# Schematic_diagram-EDA.net
KiCad netlist of a schematic drawn in EasyEDA
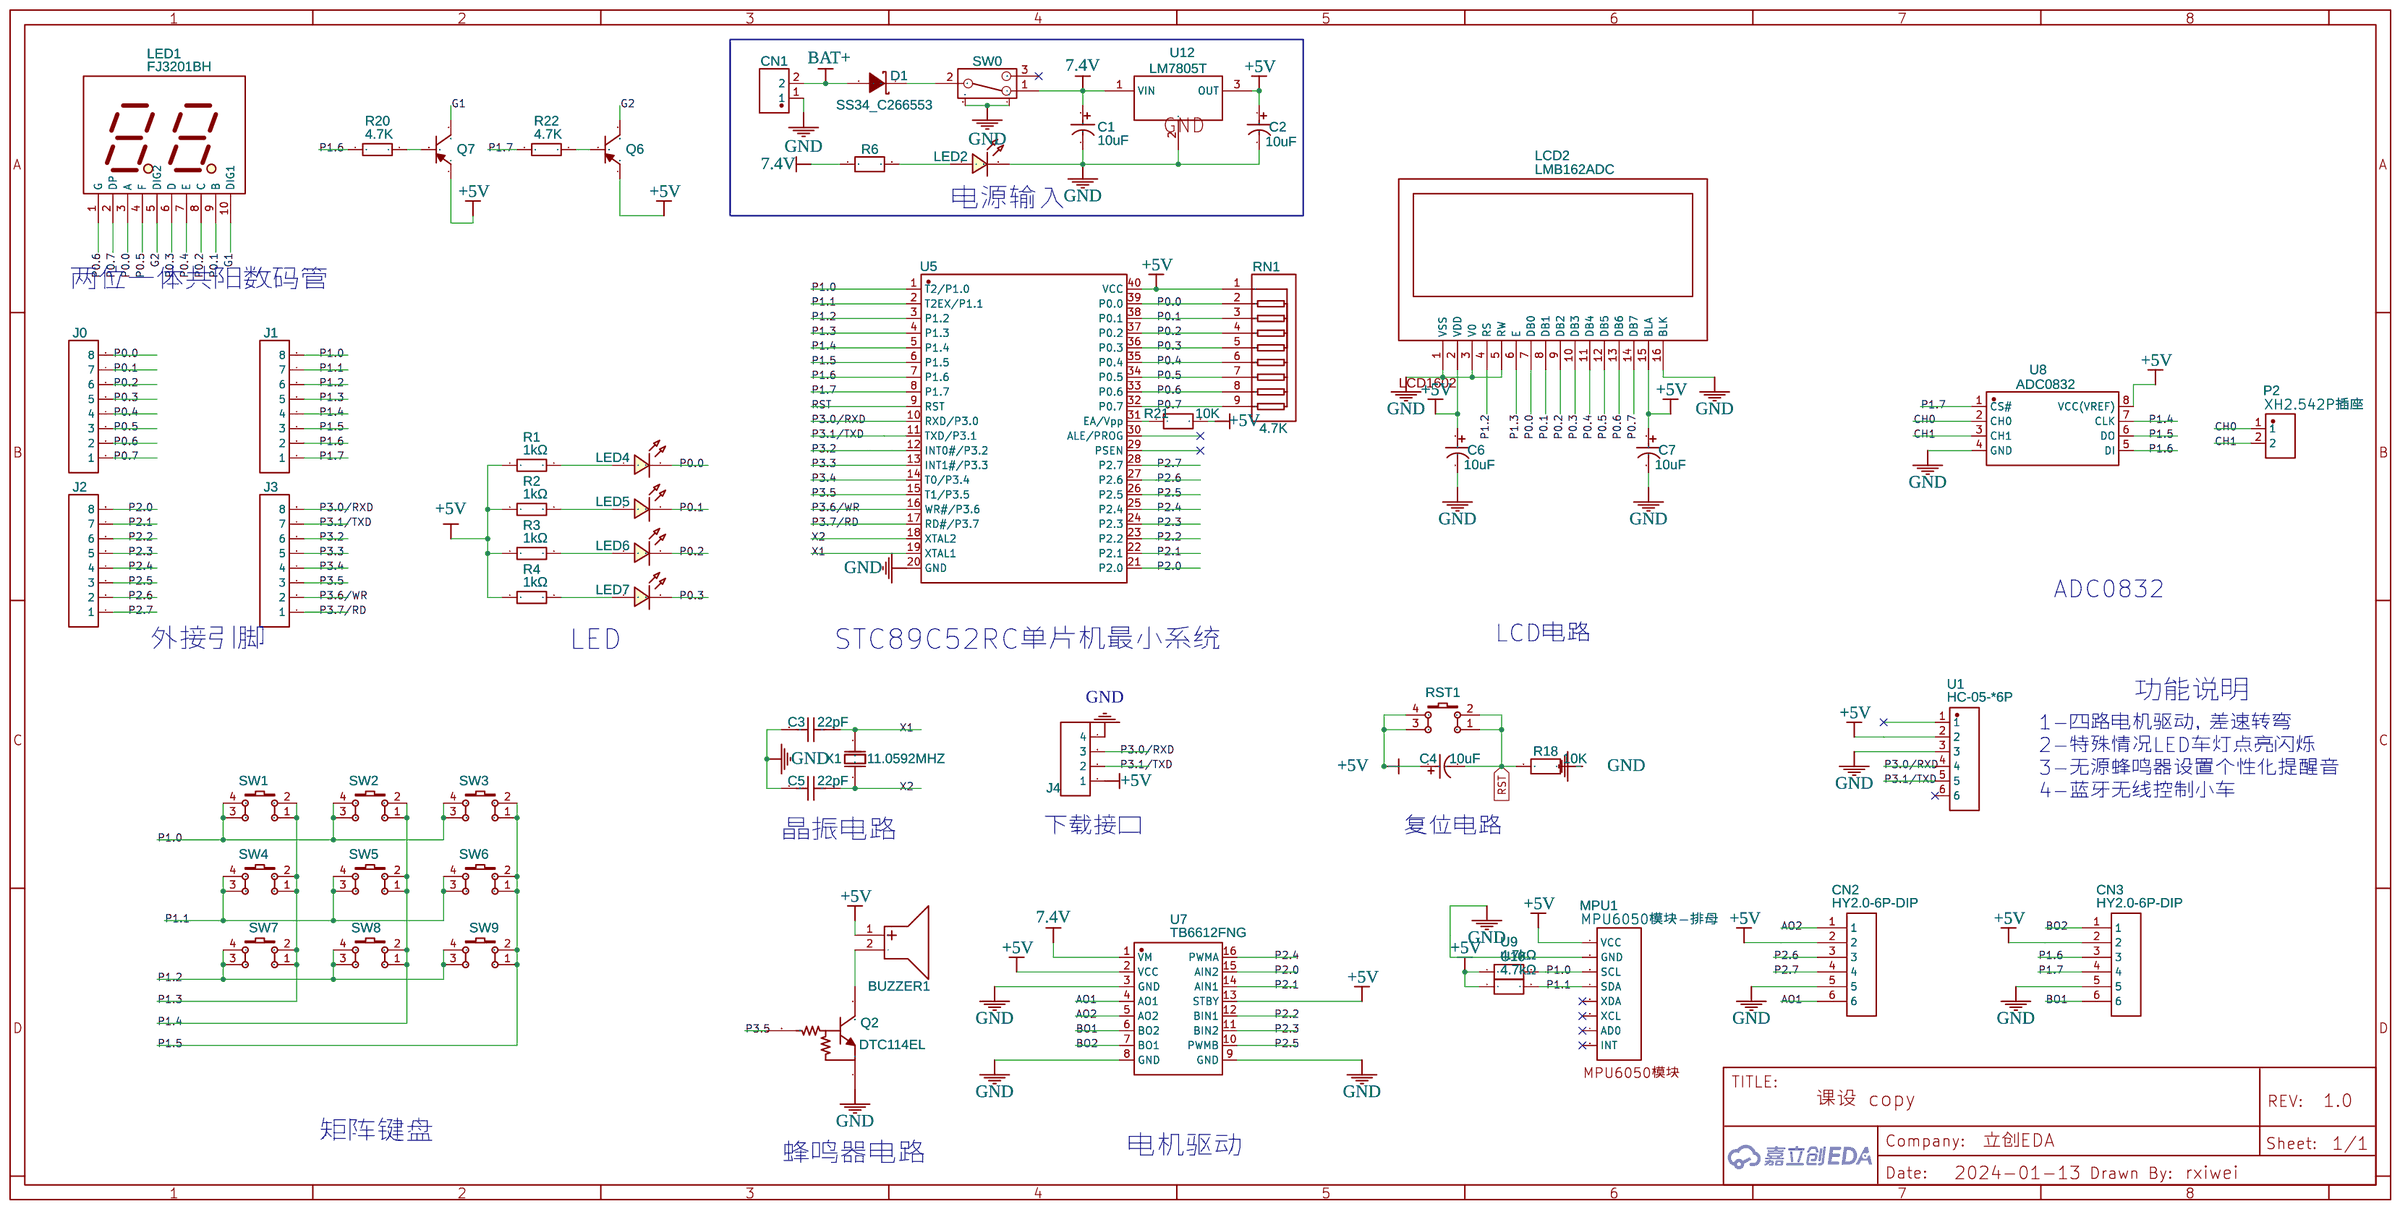
[diagram p0: schematic sheet]

(export (version "E")
  (design (tool "Eeschema 10.0.6"))
  (components
    (comp (ref "BUZZER1")
      (value "YS-MBZ9042C05R42")
      (fields (field (name "Manufacturer") "Fengming"))
      (libsource (lib "") (part "YS-MBZ9042C05R42"))
    )
    (comp (ref "C1")
      (value "10uF")
      (fields (field (name "Manufacturer Part") "10uF 25V 4*7") (field (name "Manufacturer") "ValuePro"))
      (libsource (lib "") (part "10uF 25V 4*7_1"))
    )
    (comp (ref "C2")
      (value "10uF")
      (fields (field (name "Manufacturer Part") "10uF 25V 4*7") (field (name "Manufacturer") "ValuePro"))
      (libsource (lib "") (part "10uF 25V 4*7_1"))
    )
    (comp (ref "C3") (value "22pF") (libsource (lib "") (part "CC81-N5U2J1B220KSEW")))
    (comp (ref "C4")
      (value "10uF")
      (fields (field (name "Manufacturer Part") "10uF 25V 4*7") (field (name "Manufacturer") "ValuePro"))
      (libsource (lib "") (part "10uF 25V 4*7"))
    )
    (comp (ref "C5") (value "22pF") (libsource (lib "") (part "CC81-N5U2J1B220KSEW")))
    (comp (ref "C6")
      (value "10uF")
      (fields (field (name "Manufacturer Part") "10uF 25V 4*7") (field (name "Manufacturer") "ValuePro"))
      (libsource (lib "") (part "10uF 25V 4*7_1"))
    )
    (comp (ref "C7")
      (value "10uF")
      (fields (field (name "Manufacturer Part") "10uF 25V 4*7") (field (name "Manufacturer") "ValuePro"))
      (libsource (lib "") (part "10uF 25V 4*7_1"))
    )
    (comp (ref "CN1")
      (value "XH-2A_C722856")
      (fields (field (name "Manufacturer Part") "XH-2A") (field (name "Manufacturer") "CAX"))
      (libsource (lib "") (part "XH-2A_C722856"))
    )
    (comp (ref "CN2") (value "HY2.0-6P-DIP") (libsource (lib "") (part "HY2.0-6P-DIP")))
    (comp (ref "CN3") (value "HY2.0-6P-DIP") (libsource (lib "") (part "HY2.0-6P-DIP")))
    (comp (ref "D1")
      (value "SS34_C266553")
      (fields
        (field (name "Manufacturer Part") "SS34")
        (field (name "Manufacturer") "Bourne Semicon (Shenzhen)")
      )
      (libsource (lib "") (part "SS34_C266553"))
    )
    (comp (ref "J0") (value "HDR-M-2.54_1x8") (libsource (lib "") (part "HDR-M-2.54_1x8")))
    (comp (ref "J1") (value "HDR-M-2.54_1x8") (libsource (lib "") (part "HDR-M-2.54_1x8")))
    (comp (ref "J2") (value "HDR-M-2.54_1x8") (libsource (lib "") (part "HDR-M-2.54_1x8")))
    (comp (ref "J3") (value "HDR-M-2.54_1x8") (libsource (lib "") (part "HDR-M-2.54_1x8")))
    (comp (ref "J4") (value "HDR-M-2.54_1x4") (libsource (lib "") (part "HDR-M-2.54_1x4")))
    (comp (ref "LCD2")
      (value "LMB162ADC")
      (fields (field (name "Manufacturer") "TOPWAY"))
      (libsource (lib "") (part "LMB162ADC"))
    )
    (comp (ref "LED1")
      (value "FJ3201BH")
      (fields (field (name "Manufacturer") "志浩"))
      (libsource (lib "") (part "FJ3201BH"))
    )
    (comp (ref "LED2")
      (value "LED-TH-3mm_R")
      (fields
        (field (name "Manufacturer Part") "204-10SDRD/S530-A3-L")
        (field (name "Manufacturer") "EVERLIGHT(台湾亿光)")
      )
      (libsource (lib "") (part "LED-TH-3mm_R"))
    )
    (comp (ref "LED4")
      (value "LED-TH-3mm_R")
      (fields
        (field (name "Manufacturer Part") "204-10SDRD/S530-A3-L")
        (field (name "Manufacturer") "EVERLIGHT(台湾亿光)")
      )
      (libsource (lib "") (part "LED-TH-3mm_R"))
    )
    (comp (ref "LED5")
      (value "LED-TH-3mm_R")
      (fields
        (field (name "Manufacturer Part") "204-10SDRD/S530-A3-L")
        (field (name "Manufacturer") "EVERLIGHT(台湾亿光)")
      )
      (libsource (lib "") (part "LED-TH-3mm_R"))
    )
    (comp (ref "LED6")
      (value "LED-TH-3mm_R")
      (fields
        (field (name "Manufacturer Part") "204-10SDRD/S530-A3-L")
        (field (name "Manufacturer") "EVERLIGHT(台湾亿光)")
      )
      (libsource (lib "") (part "LED-TH-3mm_R"))
    )
    (comp (ref "LED7")
      (value "LED-TH-3mm_R")
      (fields
        (field (name "Manufacturer Part") "204-10SDRD/S530-A3-L")
        (field (name "Manufacturer") "EVERLIGHT(台湾亿光)")
      )
      (libsource (lib "") (part "LED-TH-3mm_R"))
    )
    (comp (ref "MPU1") (value "MPU6050模块-排母") (libsource (lib "") (part "MPU6050模块-排母")))
    (comp (ref "P2") (value "XH2.542P插座") (libsource (lib "") (part "XH2.542P插座")))
    (comp (ref "Q2")
      (value "DTC114EL")
      (fields (field (name "Manufacturer Part") "DTC114EL-T92-K") (field (name "Manufacturer") "UTC"))
      (libsource (lib "") (part "DTC114EL-T92-K"))
    )
    (comp (ref "Q6")
      (value "2N3906(SOT-23)")
      (fields (field (name "Manufacturer Part") "2N3906S-RTK/PS") (field (name "Manufacturer") "KEC"))
      (libsource (lib "") (part "2N3906(SOT-23)"))
    )
    (comp (ref "Q7")
      (value "2N3906(SOT-23)")
      (fields (field (name "Manufacturer Part") "2N3906S-RTK/PS") (field (name "Manufacturer") "KEC"))
      (libsource (lib "") (part "2N3906(SOT-23)"))
    )
    (comp (ref "R1")
      (value "1kΩ")
      (fields (field (name "Manufacturer Part") "MOF3WS-1KΩ±5%T") (field (name "Manufacturer") "华星机电"))
      (libsource (lib "") (part "MOF3WS-1KΩ±5%T"))
    )
    (comp (ref "R2")
      (value "1kΩ")
      (fields (field (name "Manufacturer Part") "MOF3WS-1KΩ±5%T") (field (name "Manufacturer") "华星机电"))
      (libsource (lib "") (part "MOF3WS-1KΩ±5%T"))
    )
    (comp (ref "R3")
      (value "1kΩ")
      (fields (field (name "Manufacturer Part") "MOF3WS-1KΩ±5%T") (field (name "Manufacturer") "华星机电"))
      (libsource (lib "") (part "MOF3WS-1KΩ±5%T"))
    )
    (comp (ref "R4")
      (value "1kΩ")
      (fields (field (name "Manufacturer Part") "MOF3WS-1KΩ±5%T") (field (name "Manufacturer") "华星机电"))
      (libsource (lib "") (part "MOF3WS-1KΩ±5%T"))
    )
    (comp (ref "R6")
      (value "10K")
      (fields (field (name "Manufacturer Part") "RN 1/4W 10K F T/B A1") (field (name "Manufacturer") "TyoHM"))
      (libsource (lib "") (part "RN 1/4W 10K F T/B A1"))
    )
    (comp (ref "R18")
      (value "10K")
      (fields (field (name "Manufacturer Part") "RN 1/4W 10K F T/B A1") (field (name "Manufacturer") "TyoHM"))
      (libsource (lib "") (part "RN 1/4W 10K F T/B A1_1"))
    )
    (comp (ref "R20")
      (value "4.7K")
      (fields
        (field (name "Manufacturer Part") "RSS02J1001A520NH")
        (field (name "Manufacturer") "Futaba Elec")
      )
      (libsource (lib "") (part "RSS02J1001A520NH"))
    )
    (comp (ref "R21")
      (value "10K")
      (fields (field (name "Manufacturer Part") "RN 1/4W 10K F T/B A1") (field (name "Manufacturer") "TyoHM"))
      (libsource (lib "") (part "RN 1/4W 10K F T/B A1"))
    )
    (comp (ref "R22")
      (value "4.7K")
      (fields
        (field (name "Manufacturer Part") "RSS02J1001A520NH")
        (field (name "Manufacturer") "Futaba Elec")
      )
      (libsource (lib "") (part "RSS02J1001A520NH"))
    )
    (comp (ref "RN1")
      (value "4.7K")
      (fields (field (name "Manufacturer Part") "A09-472JP") (field (name "Manufacturer") "FH"))
      (libsource (lib "") (part "A09-472JP"))
    )
    (comp (ref "RST1")
      (value "K4-6×6_TH")
      (fields (field (name "Manufacturer Part") "K2-1102DP-E4SW-04") (field (name "Manufacturer") "韩国韩荣"))
      (libsource (lib "") (part "K4-6×6_TH_1"))
    )
    (comp (ref "SW0")
      (value "SK-12E12-G5")
      (fields (field (name "Manufacturer") "Rectangular Connectors - Contacts"))
      (libsource (lib "") (part "SK-12E12-G5"))
    )
    (comp (ref "SW1")
      (value "K4-6×6_TH")
      (fields (field (name "Manufacturer Part") "K2-1102DP-E4SW-04") (field (name "Manufacturer") "韩国韩荣"))
      (libsource (lib "") (part "K4-6×6_TH"))
    )
    (comp (ref "SW2")
      (value "K4-6×6_TH")
      (fields (field (name "Manufacturer Part") "K2-1102DP-E4SW-04") (field (name "Manufacturer") "韩国韩荣"))
      (libsource (lib "") (part "K4-6×6_TH"))
    )
    (comp (ref "SW3")
      (value "K4-6×6_TH")
      (fields (field (name "Manufacturer Part") "K2-1102DP-E4SW-04") (field (name "Manufacturer") "韩国韩荣"))
      (libsource (lib "") (part "K4-6×6_TH"))
    )
    (comp (ref "SW4")
      (value "K4-6×6_TH")
      (fields (field (name "Manufacturer Part") "K2-1102DP-E4SW-04") (field (name "Manufacturer") "韩国韩荣"))
      (libsource (lib "") (part "K4-6×6_TH"))
    )
    (comp (ref "SW5")
      (value "K4-6×6_TH")
      (fields (field (name "Manufacturer Part") "K2-1102DP-E4SW-04") (field (name "Manufacturer") "韩国韩荣"))
      (libsource (lib "") (part "K4-6×6_TH"))
    )
    (comp (ref "SW6")
      (value "K4-6×6_TH")
      (fields (field (name "Manufacturer Part") "K2-1102DP-E4SW-04") (field (name "Manufacturer") "韩国韩荣"))
      (libsource (lib "") (part "K4-6×6_TH"))
    )
    (comp (ref "SW7")
      (value "K4-6×6_TH")
      (fields (field (name "Manufacturer Part") "K2-1102DP-E4SW-04") (field (name "Manufacturer") "韩国韩荣"))
      (libsource (lib "") (part "K4-6×6_TH"))
    )
    (comp (ref "SW8")
      (value "K4-6×6_TH")
      (fields (field (name "Manufacturer Part") "K2-1102DP-E4SW-04") (field (name "Manufacturer") "韩国韩荣"))
      (libsource (lib "") (part "K4-6×6_TH"))
    )
    (comp (ref "SW9")
      (value "K4-6×6_TH")
      (fields (field (name "Manufacturer Part") "K2-1102DP-E4SW-04") (field (name "Manufacturer") "韩国韩荣"))
      (libsource (lib "") (part "K4-6×6_TH"))
    )
    (comp (ref "U1")
      (value "HC-05-*6P")
      (fields (field (name "Manufacturer Part") "HC-05_排母*6P"))
      (libsource (lib "") (part "HC-05-*6P"))
    )
    (comp (ref "U5")
      (value "STC89C52RC-40I")
      (fields (field (name "Manufacturer") "STC"))
      (libsource (lib "") (part "STC89C52RC-40I"))
    )
    (comp (ref "U7") (value "TB6612FNG") (libsource (lib "") (part "TB6612FNG")))
    (comp (ref "U8")
      (value "ADC0832")
      (fields (field (name "Manufacturer Part") "ADC0832CCN/NOPB") (field (name "Manufacturer") "TI(德州仪器)"))
      (libsource (lib "") (part "ADC0832CCN/NOPB"))
    )
    (comp (ref "U9")
      (value "4.7kΩ")
      (fields (field (name "Manufacturer Part") "FMF200FRE73-4K7") (field (name "Manufacturer") "YAGEO(国巨)"))
      (libsource (lib "") (part "FMF200FRE73-4K7"))
    )
    (comp (ref "U10")
      (value "4.7kΩ")
      (fields (field (name "Manufacturer Part") "FMF200FRE73-4K7") (field (name "Manufacturer") "YAGEO(国巨)"))
      (libsource (lib "") (part "FMF200FRE73-4K7"))
    )
    (comp (ref "U12")
      (value "LM7805T")
      (fields (field (name "Manufacturer") "HGC(Huaguan Semicon)"))
      (libsource (lib "") (part "LM7805T"))
    )
    (comp (ref "X1")
      (value "11.0592MHZ")
      (fields
        (field (name "Manufacturer Part") "XIHCCCNANF-11.0592")
        (field (name "Manufacturer") "TAITIEN Elec")
      )
      (libsource (lib "") (part "XIHCCCNANF-11.0592"))
    )
  )
  (nets
    (net (code "1") (name "+5V") (class "Default")
      (node (ref "BUZZER1") (pin "1") (pinfunction "+_1") (pintype "unspecified"))
      (node (ref "C2") (pin "1") (pinfunction "1_1") (pintype "input"))
      (node (ref "C4") (pin "1") (pinfunction "1_1") (pintype "input"))
      (node (ref "C6") (pin "1") (pinfunction "1_1") (pintype "input"))
      (node (ref "C7") (pin "1") (pinfunction "1_1") (pintype "input"))
      (node (ref "CN2") (pin "2") (pinfunction "2_2") (pintype "unspecified"))
      (node (ref "CN3") (pin "2") (pinfunction "2_2") (pintype "unspecified"))
      (node (ref "J4") (pin "1") (pinfunction "1_1") (pintype "unspecified"))
      (node (ref "LCD2") (pin "15") (pinfunction "BLA_15") (pintype "unspecified"))
      (node (ref "LCD2") (pin "2") (pinfunction "VDD_2") (pintype "unspecified"))
      (node (ref "MPU1") (pin "1") (pinfunction "VCC_1") (pintype "unspecified"))
      (node (ref "Q6") (pin "1") (pinfunction "E_1") (pintype "input"))
      (node (ref "Q7") (pin "1") (pinfunction "E_1") (pintype "input"))
      (node (ref "R1") (pin "1") (pinfunction "1_1") (pintype "unspecified"))
      (node (ref "R2") (pin "1") (pinfunction "1_1") (pintype "unspecified"))
      (node (ref "R21") (pin "2") (pinfunction "2_2") (pintype "unspecified"))
      (node (ref "R3") (pin "1") (pinfunction "1_1") (pintype "unspecified"))
      (node (ref "R4") (pin "1") (pinfunction "1_1") (pintype "unspecified"))
      (node (ref "RN1") (pin "1") (pinfunction "1_1") (pintype "unspecified"))
      (node (ref "RST1") (pin "3") (pinfunction "3_3") (pintype "unspecified"))
      (node (ref "RST1") (pin "4") (pinfunction "4_4") (pintype "unspecified"))
      (node (ref "U1") (pin "2") (pinfunction "2_2") (pintype "unspecified"))
      (node (ref "U10") (pin "1") (pinfunction "1_1") (pintype "unspecified"))
      (node (ref "U12") (pin "3") (pinfunction "OUT_3") (pintype "passive"))
      (node (ref "U5") (pin "40") (pinfunction "VCC_40") (pintype "unspecified"))
      (node (ref "U7") (pin "13") (pinfunction "STBY_13") (pintype "unspecified"))
      (node (ref "U7") (pin "2") (pinfunction "VCC_2") (pintype "unspecified"))
      (node (ref "U8") (pin "8") (pinfunction "VCC(VREF)_8") (pintype "unspecified"))
      (node (ref "U9") (pin "1") (pinfunction "1_1") (pintype "unspecified"))
    )
    (net (code "2") (name "/AO1") (class "Default")
      (node (ref "CN2") (pin "6") (pinfunction "6_6") (pintype "unspecified"))
      (node (ref "U7") (pin "4") (pinfunction "AO1_4") (pintype "unspecified"))
    )
    (net (code "3") (name "/AO2") (class "Default")
      (node (ref "CN2") (pin "1") (pinfunction "1_1") (pintype "unspecified"))
      (node (ref "U7") (pin "5") (pinfunction "AO2_5") (pintype "unspecified"))
    )
    (net (code "4") (name "/BO1") (class "Default")
      (node (ref "CN3") (pin "6") (pinfunction "6_6") (pintype "unspecified"))
      (node (ref "U7") (pin "6") (pinfunction "BO2_6") (pintype "unspecified"))
    )
    (net (code "5") (name "/BO2") (class "Default")
      (node (ref "CN3") (pin "1") (pinfunction "1_1") (pintype "unspecified"))
      (node (ref "U7") (pin "7") (pinfunction "BO1_7") (pintype "unspecified"))
    )
    (net (code "6") (name "/CH0") (class "Default")
      (node (ref "P2") (pin "1") (pinfunction "1_1") (pintype "unspecified"))
      (node (ref "U8") (pin "2") (pinfunction "CH0_2") (pintype "unspecified"))
    )
    (net (code "7") (name "/CH1") (class "Default")
      (node (ref "P2") (pin "2") (pinfunction "2_2") (pintype "unspecified"))
      (node (ref "U8") (pin "3") (pinfunction "CH1_3") (pintype "unspecified"))
    )
    (net (code "8") (name "/G1") (class "Default")
      (node (ref "LED1") (pin "10") (pinfunction "DIG1_10") (pintype "unspecified"))
      (node (ref "Q7") (pin "3") (pinfunction "C_3") (pintype "input"))
    )
    (net (code "9") (name "/G2") (class "Default")
      (node (ref "LED1") (pin "5") (pinfunction "DIG2_5") (pintype "unspecified"))
      (node (ref "Q6") (pin "3") (pinfunction "C_3") (pintype "input"))
    )
    (net (code "10") (name "/P0.0") (class "Default")
      (node (ref "J0") (pin "8") (pinfunction "8_8") (pintype "unspecified"))
      (node (ref "LCD2") (pin "7") (pinfunction "DB0_7") (pintype "unspecified"))
      (node (ref "LED1") (pin "3") (pinfunction "A_3") (pintype "unspecified"))
      (node (ref "LED4") (pin "2") (pinfunction "2_2") (pintype "unspecified"))
      (node (ref "RN1") (pin "2") (pinfunction "2_2") (pintype "unspecified"))
      (node (ref "U5") (pin "39") (pinfunction "P0.0_39") (pintype "unspecified"))
    )
    (net (code "11") (name "/P0.1") (class "Default")
      (node (ref "J0") (pin "7") (pinfunction "7_7") (pintype "unspecified"))
      (node (ref "LCD2") (pin "8") (pinfunction "DB1_8") (pintype "unspecified"))
      (node (ref "LED1") (pin "9") (pinfunction "B_9") (pintype "unspecified"))
      (node (ref "LED5") (pin "2") (pinfunction "2_2") (pintype "unspecified"))
      (node (ref "RN1") (pin "3") (pinfunction "3_3") (pintype "unspecified"))
      (node (ref "U5") (pin "38") (pinfunction "P0.1_38") (pintype "unspecified"))
    )
    (net (code "12") (name "/P0.2") (class "Default")
      (node (ref "J0") (pin "6") (pinfunction "6_6") (pintype "unspecified"))
      (node (ref "LCD2") (pin "9") (pinfunction "DB2_9") (pintype "unspecified"))
      (node (ref "LED1") (pin "8") (pinfunction "C_8") (pintype "unspecified"))
      (node (ref "LED6") (pin "2") (pinfunction "2_2") (pintype "unspecified"))
      (node (ref "RN1") (pin "4") (pinfunction "4_4") (pintype "unspecified"))
      (node (ref "U5") (pin "37") (pinfunction "P0.2_37") (pintype "unspecified"))
    )
    (net (code "13") (name "/P0.3") (class "Default")
      (node (ref "J0") (pin "5") (pinfunction "5_5") (pintype "unspecified"))
      (node (ref "LCD2") (pin "10") (pinfunction "DB3_10") (pintype "unspecified"))
      (node (ref "LED1") (pin "6") (pinfunction "D_6") (pintype "unspecified"))
      (node (ref "LED7") (pin "2") (pinfunction "2_2") (pintype "unspecified"))
      (node (ref "RN1") (pin "5") (pinfunction "5_5") (pintype "unspecified"))
      (node (ref "U5") (pin "36") (pinfunction "P0.3_36") (pintype "unspecified"))
    )
    (net (code "14") (name "/P0.4") (class "Default")
      (node (ref "J0") (pin "4") (pinfunction "4_4") (pintype "unspecified"))
      (node (ref "LCD2") (pin "11") (pinfunction "DB4_11") (pintype "unspecified"))
      (node (ref "LED1") (pin "7") (pinfunction "E_7") (pintype "unspecified"))
      (node (ref "RN1") (pin "6") (pinfunction "6_6") (pintype "unspecified"))
      (node (ref "U5") (pin "35") (pinfunction "P0.4_35") (pintype "unspecified"))
    )
    (net (code "15") (name "/P0.5") (class "Default")
      (node (ref "J0") (pin "3") (pinfunction "3_3") (pintype "unspecified"))
      (node (ref "LCD2") (pin "12") (pinfunction "DB5_12") (pintype "unspecified"))
      (node (ref "LED1") (pin "4") (pinfunction "F_4") (pintype "unspecified"))
      (node (ref "RN1") (pin "7") (pinfunction "7_7") (pintype "unspecified"))
      (node (ref "U5") (pin "34") (pinfunction "P0.5_34") (pintype "unspecified"))
    )
    (net (code "16") (name "/P0.6") (class "Default")
      (node (ref "J0") (pin "2") (pinfunction "2_2") (pintype "unspecified"))
      (node (ref "LCD2") (pin "13") (pinfunction "DB6_13") (pintype "unspecified"))
      (node (ref "LED1") (pin "1") (pinfunction "G_1") (pintype "unspecified"))
      (node (ref "RN1") (pin "8") (pinfunction "8_8") (pintype "unspecified"))
      (node (ref "U5") (pin "33") (pinfunction "P0.6_33") (pintype "unspecified"))
    )
    (net (code "17") (name "/P0.7") (class "Default")
      (node (ref "J0") (pin "1") (pinfunction "1_1") (pintype "unspecified"))
      (node (ref "LCD2") (pin "14") (pinfunction "DB7_14") (pintype "unspecified"))
      (node (ref "LED1") (pin "2") (pinfunction "DP_2") (pintype "unspecified"))
      (node (ref "RN1") (pin "9") (pinfunction "9_9") (pintype "unspecified"))
      (node (ref "U5") (pin "32") (pinfunction "P0.7_32") (pintype "unspecified"))
    )
    (net (code "18") (name "/P1.0") (class "Default")
      (node (ref "J1") (pin "8") (pinfunction "8_8") (pintype "unspecified"))
      (node (ref "MPU1") (pin "3") (pinfunction "SCL_3") (pintype "unspecified"))
      (node (ref "SW1") (pin "3") (pinfunction "3_3") (pintype "unspecified"))
      (node (ref "SW1") (pin "4") (pinfunction "4_4") (pintype "unspecified"))
      (node (ref "SW2") (pin "3") (pinfunction "3_3") (pintype "unspecified"))
      (node (ref "SW2") (pin "4") (pinfunction "4_4") (pintype "unspecified"))
      (node (ref "SW3") (pin "3") (pinfunction "3_3") (pintype "unspecified"))
      (node (ref "SW3") (pin "4") (pinfunction "4_4") (pintype "unspecified"))
      (node (ref "U5") (pin "1") (pinfunction "T2/P1.0_1") (pintype "unspecified"))
      (node (ref "U9") (pin "2") (pinfunction "2_2") (pintype "unspecified"))
    )
    (net (code "19") (name "/P1.1") (class "Default")
      (node (ref "J1") (pin "7") (pinfunction "7_7") (pintype "unspecified"))
      (node (ref "MPU1") (pin "4") (pinfunction "SDA_4") (pintype "unspecified"))
      (node (ref "SW4") (pin "3") (pinfunction "3_3") (pintype "unspecified"))
      (node (ref "SW4") (pin "4") (pinfunction "4_4") (pintype "unspecified"))
      (node (ref "SW5") (pin "3") (pinfunction "3_3") (pintype "unspecified"))
      (node (ref "SW5") (pin "4") (pinfunction "4_4") (pintype "unspecified"))
      (node (ref "SW6") (pin "3") (pinfunction "3_3") (pintype "unspecified"))
      (node (ref "SW6") (pin "4") (pinfunction "4_4") (pintype "unspecified"))
      (node (ref "U10") (pin "2") (pinfunction "2_2") (pintype "unspecified"))
      (node (ref "U5") (pin "2") (pinfunction "T2EX/P1.1_2") (pintype "unspecified"))
    )
    (net (code "20") (name "/P1.2") (class "Default")
      (node (ref "J1") (pin "6") (pinfunction "6_6") (pintype "unspecified"))
      (node (ref "LCD2") (pin "4") (pinfunction "RS_4") (pintype "unspecified"))
      (node (ref "SW7") (pin "3") (pinfunction "3_3") (pintype "unspecified"))
      (node (ref "SW7") (pin "4") (pinfunction "4_4") (pintype "unspecified"))
      (node (ref "SW8") (pin "3") (pinfunction "3_3") (pintype "unspecified"))
      (node (ref "SW8") (pin "4") (pinfunction "4_4") (pintype "unspecified"))
      (node (ref "SW9") (pin "3") (pinfunction "3_3") (pintype "unspecified"))
      (node (ref "SW9") (pin "4") (pinfunction "4_4") (pintype "unspecified"))
      (node (ref "U5") (pin "3") (pinfunction "P1.2_3") (pintype "unspecified"))
    )
    (net (code "21") (name "/P1.3") (class "Default")
      (node (ref "J1") (pin "5") (pinfunction "5_5") (pintype "unspecified"))
      (node (ref "LCD2") (pin "6") (pinfunction "E_6") (pintype "unspecified"))
      (node (ref "SW1") (pin "1") (pinfunction "1_1") (pintype "unspecified"))
      (node (ref "SW1") (pin "2") (pinfunction "2_2") (pintype "unspecified"))
      (node (ref "SW4") (pin "1") (pinfunction "1_1") (pintype "unspecified"))
      (node (ref "SW4") (pin "2") (pinfunction "2_2") (pintype "unspecified"))
      (node (ref "SW7") (pin "1") (pinfunction "1_1") (pintype "unspecified"))
      (node (ref "SW7") (pin "2") (pinfunction "2_2") (pintype "unspecified"))
      (node (ref "U5") (pin "4") (pinfunction "P1.3_4") (pintype "unspecified"))
    )
    (net (code "22") (name "/P1.4") (class "Default")
      (node (ref "J1") (pin "4") (pinfunction "4_4") (pintype "unspecified"))
      (node (ref "SW2") (pin "1") (pinfunction "1_1") (pintype "unspecified"))
      (node (ref "SW2") (pin "2") (pinfunction "2_2") (pintype "unspecified"))
      (node (ref "SW5") (pin "1") (pinfunction "1_1") (pintype "unspecified"))
      (node (ref "SW5") (pin "2") (pinfunction "2_2") (pintype "unspecified"))
      (node (ref "SW8") (pin "1") (pinfunction "1_1") (pintype "unspecified"))
      (node (ref "SW8") (pin "2") (pinfunction "2_2") (pintype "unspecified"))
      (node (ref "U5") (pin "5") (pinfunction "P1.4_5") (pintype "unspecified"))
      (node (ref "U8") (pin "7") (pinfunction "CLK_7") (pintype "unspecified"))
    )
    (net (code "23") (name "/P1.5") (class "Default")
      (node (ref "J1") (pin "3") (pinfunction "3_3") (pintype "unspecified"))
      (node (ref "SW3") (pin "1") (pinfunction "1_1") (pintype "unspecified"))
      (node (ref "SW3") (pin "2") (pinfunction "2_2") (pintype "unspecified"))
      (node (ref "SW6") (pin "1") (pinfunction "1_1") (pintype "unspecified"))
      (node (ref "SW6") (pin "2") (pinfunction "2_2") (pintype "unspecified"))
      (node (ref "SW9") (pin "1") (pinfunction "1_1") (pintype "unspecified"))
      (node (ref "SW9") (pin "2") (pinfunction "2_2") (pintype "unspecified"))
      (node (ref "U5") (pin "6") (pinfunction "P1.5_6") (pintype "unspecified"))
      (node (ref "U8") (pin "6") (pinfunction "DO_6") (pintype "unspecified"))
    )
    (net (code "24") (name "/P1.6") (class "Default")
      (node (ref "CN3") (pin "3") (pinfunction "3_3") (pintype "unspecified"))
      (node (ref "J1") (pin "2") (pinfunction "2_2") (pintype "unspecified"))
      (node (ref "R20") (pin "2") (pinfunction "2_2") (pintype "unspecified"))
      (node (ref "U5") (pin "7") (pinfunction "P1.6_7") (pintype "unspecified"))
      (node (ref "U8") (pin "5") (pinfunction "DI_5") (pintype "unspecified"))
    )
    (net (code "25") (name "/P1.7") (class "Default")
      (node (ref "CN3") (pin "4") (pinfunction "4_4") (pintype "unspecified"))
      (node (ref "J1") (pin "1") (pinfunction "1_1") (pintype "unspecified"))
      (node (ref "R22") (pin "2") (pinfunction "2_2") (pintype "unspecified"))
      (node (ref "U5") (pin "8") (pinfunction "P1.7_8") (pintype "unspecified"))
      (node (ref "U8") (pin "1") (pinfunction "CS#_1") (pintype "unspecified"))
    )
    (net (code "26") (name "/P2.0") (class "Default")
      (node (ref "J2") (pin "8") (pinfunction "8_8") (pintype "unspecified"))
      (node (ref "U5") (pin "21") (pinfunction "P2.0_21") (pintype "unspecified"))
      (node (ref "U7") (pin "15") (pinfunction "AIN2_15") (pintype "unspecified"))
    )
    (net (code "27") (name "/P2.1") (class "Default")
      (node (ref "J2") (pin "7") (pinfunction "7_7") (pintype "unspecified"))
      (node (ref "U5") (pin "22") (pinfunction "P2.1_22") (pintype "unspecified"))
      (node (ref "U7") (pin "14") (pinfunction "AIN1_14") (pintype "unspecified"))
    )
    (net (code "28") (name "/P2.2") (class "Default")
      (node (ref "J2") (pin "6") (pinfunction "6_6") (pintype "unspecified"))
      (node (ref "U5") (pin "23") (pinfunction "P2.2_23") (pintype "unspecified"))
      (node (ref "U7") (pin "12") (pinfunction "BIN1_12") (pintype "unspecified"))
    )
    (net (code "29") (name "/P2.3") (class "Default")
      (node (ref "J2") (pin "5") (pinfunction "5_5") (pintype "unspecified"))
      (node (ref "U5") (pin "24") (pinfunction "P2.3_24") (pintype "unspecified"))
      (node (ref "U7") (pin "11") (pinfunction "BIN2_11") (pintype "unspecified"))
    )
    (net (code "30") (name "/P2.4") (class "Default")
      (node (ref "J2") (pin "4") (pinfunction "4_4") (pintype "unspecified"))
      (node (ref "U5") (pin "25") (pinfunction "P2.4_25") (pintype "unspecified"))
      (node (ref "U7") (pin "16") (pinfunction "PWMA_16") (pintype "unspecified"))
    )
    (net (code "31") (name "/P2.5") (class "Default")
      (node (ref "J2") (pin "3") (pinfunction "3_3") (pintype "unspecified"))
      (node (ref "U5") (pin "26") (pinfunction "P2.5_26") (pintype "unspecified"))
      (node (ref "U7") (pin "10") (pinfunction "PWMB_10") (pintype "unspecified"))
    )
    (net (code "32") (name "/P2.6") (class "Default")
      (node (ref "CN2") (pin "3") (pinfunction "3_3") (pintype "unspecified"))
      (node (ref "J2") (pin "2") (pinfunction "2_2") (pintype "unspecified"))
      (node (ref "U5") (pin "27") (pinfunction "P2.6_27") (pintype "unspecified"))
    )
    (net (code "33") (name "/P2.7") (class "Default")
      (node (ref "CN2") (pin "4") (pinfunction "4_4") (pintype "unspecified"))
      (node (ref "J2") (pin "1") (pinfunction "1_1") (pintype "unspecified"))
      (node (ref "U5") (pin "28") (pinfunction "P2.7_28") (pintype "unspecified"))
    )
    (net (code "34") (name "/P3.0{slash}RXD") (class "Default")
      (node (ref "J3") (pin "8") (pinfunction "8_8") (pintype "unspecified"))
      (node (ref "J4") (pin "3") (pinfunction "3_3") (pintype "unspecified"))
      (node (ref "U1") (pin "4") (pinfunction "4_4") (pintype "unspecified"))
      (node (ref "U5") (pin "10") (pinfunction "RXD/P3.0_10") (pintype "unspecified"))
    )
    (net (code "35") (name "/P3.1{slash}TXD") (class "Default")
      (node (ref "J3") (pin "7") (pinfunction "7_7") (pintype "unspecified"))
      (node (ref "J4") (pin "2") (pinfunction "2_2") (pintype "unspecified"))
      (node (ref "U1") (pin "5") (pinfunction "5_5") (pintype "unspecified"))
      (node (ref "U5") (pin "11") (pinfunction "TXD/P3.1_11") (pintype "unspecified"))
    )
    (net (code "36") (name "/P3.2") (class "Default")
      (node (ref "J3") (pin "6") (pinfunction "6_6") (pintype "unspecified"))
      (node (ref "U5") (pin "12") (pinfunction "INT0#/P3.2_12") (pintype "unspecified"))
    )
    (net (code "37") (name "/P3.3") (class "Default")
      (node (ref "J3") (pin "5") (pinfunction "5_5") (pintype "unspecified"))
      (node (ref "U5") (pin "13") (pinfunction "INT1#/P3.3_13") (pintype "unspecified"))
    )
    (net (code "38") (name "/P3.4") (class "Default")
      (node (ref "J3") (pin "4") (pinfunction "4_4") (pintype "unspecified"))
      (node (ref "U5") (pin "14") (pinfunction "T0/P3.4_14") (pintype "unspecified"))
    )
    (net (code "39") (name "/P3.5") (class "Default")
      (node (ref "J3") (pin "3") (pinfunction "3_3") (pintype "unspecified"))
      (node (ref "Q2") (pin "3") (pinfunction "B_3") (pintype "unspecified"))
      (node (ref "U5") (pin "15") (pinfunction "T1/P3.5_15") (pintype "unspecified"))
    )
    (net (code "40") (name "/P3.6{slash}WR") (class "Default")
      (node (ref "J3") (pin "2") (pinfunction "2_2") (pintype "unspecified"))
      (node (ref "U5") (pin "16") (pinfunction "WR#/P3.6_16") (pintype "unspecified"))
    )
    (net (code "41") (name "/P3.7{slash}RD") (class "Default")
      (node (ref "J3") (pin "1") (pinfunction "1_1") (pintype "unspecified"))
      (node (ref "U5") (pin "17") (pinfunction "RD#/P3.7_17") (pintype "unspecified"))
    )
    (net (code "42") (name "/X1") (class "Default")
      (node (ref "C3") (pin "1") (pinfunction "1_1") (pintype "unspecified"))
      (node (ref "U5") (pin "19") (pinfunction "XTAL1_19") (pintype "unspecified"))
      (node (ref "X1") (pin "2") (pinfunction "OSC2_2") (pintype "input"))
    )
    (net (code "43") (name "/X2") (class "Default")
      (node (ref "C5") (pin "1") (pinfunction "1_1") (pintype "unspecified"))
      (node (ref "U5") (pin "18") (pinfunction "XTAL2_18") (pintype "unspecified"))
      (node (ref "X1") (pin "1") (pinfunction "OSC1_1") (pintype "input"))
    )
    (net (code "44") (name "7.4V") (class "Default")
      (node (ref "C1") (pin "1") (pinfunction "1_1") (pintype "input"))
      (node (ref "R6") (pin "1") (pinfunction "1_1") (pintype "unspecified"))
      (node (ref "SW0") (pin "1") (pinfunction "1_1") (pintype "unspecified"))
      (node (ref "U12") (pin "1") (pinfunction "VIN_1") (pintype "passive"))
      (node (ref "U7") (pin "1") (pinfunction "VM_1") (pintype "unspecified"))
    )
    (net (code "45") (name "BAT+") (class "Default")
      (node (ref "CN1") (pin "2") (pinfunction "2_2") (pintype "unspecified"))
      (node (ref "D1") (pin "2") (pinfunction "A_2") (pintype "unspecified"))
    )
    (net (code "46") (name "GND") (class "Default")
      (node (ref "C1") (pin "2") (pinfunction "2_2") (pintype "input"))
      (node (ref "C2") (pin "2") (pinfunction "2_2") (pintype "input"))
      (node (ref "C3") (pin "2") (pinfunction "2_2") (pintype "unspecified"))
      (node (ref "C5") (pin "2") (pinfunction "2_2") (pintype "unspecified"))
      (node (ref "C6") (pin "2") (pinfunction "2_2") (pintype "input"))
      (node (ref "C7") (pin "2") (pinfunction "2_2") (pintype "input"))
      (node (ref "CN1") (pin "1") (pinfunction "1_1") (pintype "unspecified"))
      (node (ref "CN2") (pin "5") (pinfunction "5_5") (pintype "unspecified"))
      (node (ref "CN3") (pin "5") (pinfunction "5_5") (pintype "unspecified"))
      (node (ref "J4") (pin "4") (pinfunction "4_4") (pintype "unspecified"))
      (node (ref "LCD2") (pin "1") (pinfunction "VSS_1") (pintype "unspecified"))
      (node (ref "LCD2") (pin "16") (pinfunction "BLK_16") (pintype "unspecified"))
      (node (ref "LCD2") (pin "3") (pinfunction "V0_3") (pintype "unspecified"))
      (node (ref "LCD2") (pin "5") (pinfunction "RW_5") (pintype "unspecified"))
      (node (ref "LED2") (pin "2") (pinfunction "2_2") (pintype "unspecified"))
      (node (ref "MPU1") (pin "2") (pinfunction "GND_2") (pintype "unspecified"))
      (node (ref "Q2") (pin "1") (pinfunction "E_1") (pintype "unspecified"))
      (node (ref "R18") (pin "1") (pinfunction "1_1") (pintype "unspecified"))
      (node (ref "SW0") (pin "4") (pinfunction "4_4") (pintype "unspecified"))
      (node (ref "SW0") (pin "5") (pinfunction "5_5") (pintype "unspecified"))
      (node (ref "U1") (pin "3") (pinfunction "3_3") (pintype "unspecified"))
      (node (ref "U12") (pin "2") (pinfunction "GND_2") (pintype "passive"))
      (node (ref "U5") (pin "20") (pinfunction "GND_20") (pintype "unspecified"))
      (node (ref "U7") (pin "3") (pinfunction "GND_3") (pintype "unspecified"))
      (node (ref "U7") (pin "8") (pinfunction "GND_8") (pintype "unspecified"))
      (node (ref "U7") (pin "9") (pinfunction "GND_9") (pintype "unspecified"))
      (node (ref "U8") (pin "4") (pinfunction "GND_4") (pintype "unspecified"))
    )
    (net (code "47") (name "Net-(BUZZER1--)") (class "Default")
      (node (ref "BUZZER1") (pin "2") (pinfunction "-_2") (pintype "unspecified"))
      (node (ref "Q2") (pin "2") (pinfunction "C_2") (pintype "unspecified"))
    )
    (net (code "48") (name "Net-(D1-C)") (class "Default")
      (node (ref "D1") (pin "1") (pinfunction "C_1") (pintype "unspecified"))
      (node (ref "SW0") (pin "2") (pinfunction "2_2") (pintype "unspecified"))
    )
    (net (code "49") (name "Net-(LED2-Pad1)") (class "Default")
      (node (ref "LED2") (pin "1") (pinfunction "1_1") (pintype "unspecified"))
      (node (ref "R6") (pin "2") (pinfunction "2_2") (pintype "unspecified"))
    )
    (net (code "50") (name "Net-(LED4-Pad1)") (class "Default")
      (node (ref "LED4") (pin "1") (pinfunction "1_1") (pintype "unspecified"))
      (node (ref "R1") (pin "2") (pinfunction "2_2") (pintype "unspecified"))
    )
    (net (code "51") (name "Net-(LED5-Pad1)") (class "Default")
      (node (ref "LED5") (pin "1") (pinfunction "1_1") (pintype "unspecified"))
      (node (ref "R2") (pin "2") (pinfunction "2_2") (pintype "unspecified"))
    )
    (net (code "52") (name "Net-(LED6-Pad1)") (class "Default")
      (node (ref "LED6") (pin "1") (pinfunction "1_1") (pintype "unspecified"))
      (node (ref "R3") (pin "2") (pinfunction "2_2") (pintype "unspecified"))
    )
    (net (code "53") (name "Net-(LED7-Pad1)") (class "Default")
      (node (ref "LED7") (pin "1") (pinfunction "1_1") (pintype "unspecified"))
      (node (ref "R4") (pin "2") (pinfunction "2_2") (pintype "unspecified"))
    )
    (net (code "54") (name "Net-(Q6-B)") (class "Default")
      (node (ref "Q6") (pin "2") (pinfunction "B_2") (pintype "input"))
      (node (ref "R22") (pin "1") (pinfunction "1_1") (pintype "unspecified"))
    )
    (net (code "55") (name "Net-(Q7-B)") (class "Default")
      (node (ref "Q7") (pin "2") (pinfunction "B_2") (pintype "input"))
      (node (ref "R20") (pin "1") (pinfunction "1_1") (pintype "unspecified"))
    )
    (net (code "56") (name "Net-(U5-EA{slash}Vpp)") (class "Default")
      (node (ref "R21") (pin "1") (pinfunction "1_1") (pintype "unspecified"))
      (node (ref "U5") (pin "31") (pinfunction "EA/Vpp_31") (pintype "unspecified"))
    )
    (net (code "57") (name "RST") (class "Default")
      (node (ref "C4") (pin "2") (pinfunction "2_2") (pintype "input"))
      (node (ref "R18") (pin "2") (pinfunction "2_2") (pintype "unspecified"))
      (node (ref "RST1") (pin "1") (pinfunction "1_1") (pintype "unspecified"))
      (node (ref "RST1") (pin "2") (pinfunction "2_2") (pintype "unspecified"))
      (node (ref "U5") (pin "9") (pinfunction "RST_9") (pintype "unspecified"))
    )
    (net (code "58") (name "unconnected-(MPU1-AD0-Pad7)") (class "Default")
      (node (ref "MPU1") (pin "7") (pinfunction "AD0_7") (pintype "unspecified+no_connect"))
    )
    (net (code "59") (name "unconnected-(MPU1-INT-Pad8)") (class "Default")
      (node (ref "MPU1") (pin "8") (pinfunction "INT_8") (pintype "unspecified+no_connect"))
    )
    (net (code "60") (name "unconnected-(MPU1-XCL-Pad6)") (class "Default")
      (node (ref "MPU1") (pin "6") (pinfunction "XCL_6") (pintype "unspecified+no_connect"))
    )
    (net (code "61") (name "unconnected-(MPU1-XDA-Pad5)") (class "Default")
      (node (ref "MPU1") (pin "5") (pinfunction "XDA_5") (pintype "unspecified+no_connect"))
    )
    (net (code "62") (name "unconnected-(SW0-Pad3)") (class "Default")
      (node (ref "SW0") (pin "3") (pinfunction "3_3") (pintype "unspecified+no_connect"))
    )
    (net (code "63") (name "unconnected-(U1-Pad1)") (class "Default")
      (node (ref "U1") (pin "1") (pinfunction "1_1") (pintype "unspecified+no_connect"))
    )
    (net (code "64") (name "unconnected-(U1-Pad6)") (class "Default")
      (node (ref "U1") (pin "6") (pinfunction "6_6") (pintype "unspecified+no_connect"))
    )
    (net (code "65") (name "unconnected-(U5-ALE{slash}PROG-Pad30)") (class "Default")
      (node (ref "U5") (pin "30") (pinfunction "ALE/PROG_30") (pintype "unspecified+no_connect"))
    )
    (net (code "66") (name "unconnected-(U5-PSEN-Pad29)") (class "Default")
      (node (ref "U5") (pin "29") (pinfunction "PSEN_29") (pintype "unspecified+no_connect"))
    )
  )
)
